# Sheet1.net
KiCad netlist of a schematic drawn in Altium Designer
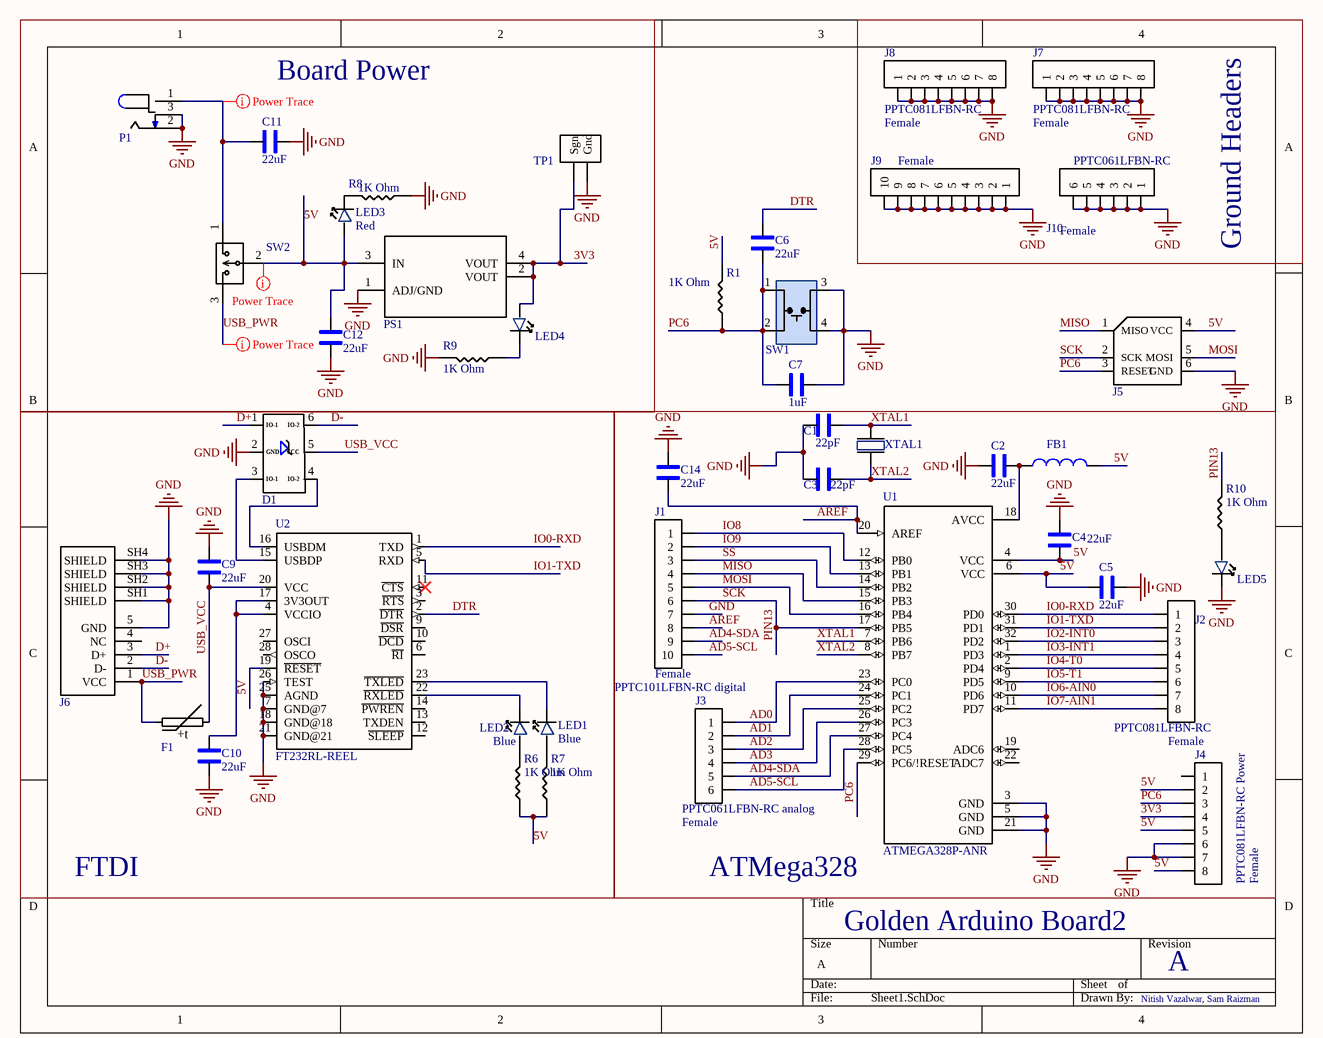
[diagram p0: Sheet1.SchDoc]

(export (version "E")
  (design (tool "Eeschema 10.0.6"))
  (components
    (comp (ref "C1")
      (value "22pF")
      (footprint "0402_Passive")
      (description "MULTILAYER CERAMIC CAPACITORS MLCC - SMD/SMT 22PF 50V 0402 ROHS")
      (fields (field (name "MFR PART #") "0402CG220J500NT") (field (name "LCSC PART#") "C1555"))
      (libsource (lib "ECEN5730Lib_2020_09_AR") (part "C_22pF_0402"))
    )
    (comp (ref "C2")
      (value "22uF")
      (footprint "0603_PASSIVE")
      (description "MULTILAYER CERAMIC CAPACITORS MLCC - SMD/SMT 22UF 6.3V 0603 ROHS")
      (fields (field (name "MFR PART #") "CL10A226MQ8NRNC") (field (name "LCSC PART#") "C59461"))
      (libsource (lib "ECEN5730Lib_2020_09_AR") (part "C_22uF_0603"))
    )
    (comp (ref "C3")
      (value "22pF")
      (footprint "0402_Passive")
      (description "MULTILAYER CERAMIC CAPACITORS MLCC - SMD/SMT 22PF 50V 0402 ROHS")
      (fields (field (name "MFR PART #") "0402CG220J500NT") (field (name "LCSC PART#") "C1555"))
      (libsource (lib "ECEN5730Lib_2020_09_AR") (part "C_22pF_0402"))
    )
    (comp (ref "C4")
      (value "22uF")
      (footprint "0603_PASSIVE")
      (description "MULTILAYER CERAMIC CAPACITORS MLCC - SMD/SMT 22UF 6.3V 0603 ROHS")
      (fields (field (name "MFR PART #") "CL10A226MQ8NRNC") (field (name "LCSC PART#") "C59461"))
      (libsource (lib "ECEN5730Lib_2020_09_AR") (part "C_22uF_0603"))
    )
    (comp (ref "C5")
      (value "22uF")
      (footprint "0603_PASSIVE")
      (description "MULTILAYER CERAMIC CAPACITORS MLCC - SMD/SMT 22UF 6.3V 0603 ROHS")
      (fields (field (name "MFR PART #") "CL10A226MQ8NRNC") (field (name "LCSC PART#") "C59461"))
      (libsource (lib "ECEN5730Lib_2020_09_AR") (part "C_22uF_0603"))
    )
    (comp (ref "C6")
      (value "22uF")
      (footprint "0603_PASSIVE")
      (description "MULTILAYER CERAMIC CAPACITORS MLCC - SMD/SMT 22UF 6.3V 0603 ROHS")
      (fields (field (name "MFR PART #") "CL10A226MQ8NRNC") (field (name "LCSC PART#") "C59461"))
      (libsource (lib "ECEN5730Lib_2020_09_AR") (part "C_22uF_0603"))
    )
    (comp (ref "C7")
      (value "1uF")
      (footprint "0402_Passive")
      (description "MULTILAYER CERAMIC CAPACITORS MLCC - SMD/SMT 1UF 25V 0402 ROHS")
      (fields (field (name "MFR PART #") "CL05A105KA5NQNC") (field (name "LCSC PART#") "C52923"))
      (libsource (lib "ECEN5730Lib_2020_09_AR") (part "C_1uF_0402"))
    )
    (comp (ref "C9")
      (value "22uF")
      (footprint "0603_PASSIVE")
      (description "MULTILAYER CERAMIC CAPACITORS MLCC - SMD/SMT 22UF 6.3V 0603 ROHS")
      (fields (field (name "MFR PART #") "CL10A226MQ8NRNC") (field (name "LCSC PART#") "C59461"))
      (libsource (lib "ECEN5730Lib_2020_09_AR") (part "C_22uF_0603"))
    )
    (comp (ref "C10")
      (value "22uF")
      (footprint "0603_PASSIVE")
      (description "MULTILAYER CERAMIC CAPACITORS MLCC - SMD/SMT 22UF 6.3V 0603 ROHS")
      (fields (field (name "MFR PART #") "CL10A226MQ8NRNC") (field (name "LCSC PART#") "C59461"))
      (libsource (lib "ECEN5730Lib_2020_09_AR") (part "C_22uF_0603"))
    )
    (comp (ref "C11")
      (value "22uF")
      (footprint "0603_PASSIVE")
      (description "MULTILAYER CERAMIC CAPACITORS MLCC - SMD/SMT 22UF 6.3V 0603 ROHS")
      (fields (field (name "MFR PART #") "CL10A226MQ8NRNC") (field (name "LCSC PART#") "C59461"))
      (libsource (lib "ECEN5730Lib_2020_09_AR") (part "C_22uF_0603"))
    )
    (comp (ref "C12")
      (value "22uF")
      (footprint "0603_PASSIVE")
      (description "MULTILAYER CERAMIC CAPACITORS MLCC - SMD/SMT 22UF 6.3V 0603 ROHS")
      (fields (field (name "MFR PART #") "CL10A226MQ8NRNC") (field (name "LCSC PART#") "C59461"))
      (libsource (lib "ECEN5730Lib_2020_09_AR") (part "C_22uF_0603"))
    )
    (comp (ref "C14")
      (value "22uF")
      (footprint "0603_PASSIVE")
      (description "MULTILAYER CERAMIC CAPACITORS MLCC - SMD/SMT 22UF 6.3V 0603 ROHS")
      (fields (field (name "MFR PART #") "CL10A226MQ8NRNC") (field (name "LCSC PART#") "C59461"))
      (libsource (lib "ECEN5730Lib_2020_09_AR") (part "C_22uF_0603"))
    )
    (comp (ref "D1")
      (value "IP4234CZ6,125")
      (footprint "TVS")
      (description "Clamp Ipp Tvs Diode Surface Mount 6-TSOP")
      (fields (field (name "DIGIKEY PART") "1727-4717-1-ND") (field (name "LCSC PART#") "C455086"))
      (libsource (lib "ECEN5730Lib_2020_09_AR") (part "D_TVS_Diode"))
    )
    (comp (ref "F1")
      (value "MF-MSMF050-2")
      (footprint "FUSE")
      (description "Polymeric PTC Resettable Fuse 15V 500mA Ih Surface Mount 1812 (4532 Metric), Concave")
      (fields (field (name "DIGIKEY PART") "MF-MSMF050-2CT-ND") (field (name "MFR PART #") "SMD1812P050TF"))
      (libsource (lib "ECEN5730Lib_2020_09_AR") (part "F_Polyswitch_500mA"))
    )
    (comp (ref "FB1")
      (value "FB_300mA_1206")
      (footprint "1206_Passive")
      (description "Ferrite Bead. 2 kOhms @ 30MHz, 500mOhm")
      (fields (field (name "MFR PART #") "NA"))
      (libsource (lib "ECEN5730Lib_2020_09_AR") (part "FB_300mA_1206"))
    )
    (comp (ref "J1")
      (value "PPTC101LFBN-RC digital")
      (footprint "10_PIN_ARDUINO_100MIL")
      (description "10 Position Header Connector 0.100\" (2.54mm) Through Hole Tin")
      (fields (field (name "DIGIKEY PART") "S7008-ND") (field (name "ALTIUM_VALUE") "Female"))
      (libsource (lib "ECEN5730Lib_2020_09_AR") (part "JF_10_PIN_FEMALE_ARDUINO"))
    )
    (comp (ref "J2")
      (value "PPTC081LFBN-RC")
      (footprint "8_PIN_ARDUINO_100MIL")
      (description "8 Position Header Connector 0.100\" (2.54mm) Through Hole Tin")
      (fields (field (name "DIGIKEY PART") "S7006-ND") (field (name "ALTIUM_VALUE") "Female"))
      (libsource (lib "") (part "JF_8_PIN_FEMALE_ARDUINO_1"))
    )
    (comp (ref "J3")
      (value "PPTC061LFBN-RC analog")
      (footprint "6_PIN_ARDUINO_100mil")
      (description "6 Position Header Connector 0.100\" (2.54mm) Through Hole Tin")
      (fields (field (name "DIGIKEY PART") "S7004-ND") (field (name "ALTIUM_VALUE") "Female"))
      (libsource (lib "") (part "JF_6_PIN_FEMALE_ARDUINO_1"))
    )
    (comp (ref "J4")
      (value "PPTC081LFBN-RC Power")
      (footprint "8_PIN_ARDUINO_100MIL")
      (description "8 Position Header Connector 0.100\" (2.54mm) Through Hole Tin")
      (fields (field (name "DIGIKEY PART") "S7006-ND") (field (name "ALTIUM_VALUE") "Female"))
      (libsource (lib "") (part "JF_8_PIN_FEMALE_ARDUINO_1"))
    )
    (comp (ref "J5")
      (value "NRPN032PAEN-RC")
      (footprint "ICSP")
      (description "Connector Header Through Hole 6 position 0.079\" (2.00mm)")
      (fields (field (name "DIGIKEY PART") "S5801-03-ND"))
      (libsource (lib "ECEN5730Lib_2020_09_AR") (part "J_ICSP"))
    )
    (comp (ref "J6")
      (value "XM7D-0512")
      (footprint "USB_2")
      (description "USB - mini B USB 2.0 Receptacle Connector 5 Position Through Hole, Right Angle")
      (fields (field (name "DIGIKEY PART") "OR1205-ND"))
      (libsource (lib "ECEN5730Lib_2020_09_AR") (part "J_USB_2_B_Mini"))
    )
    (comp (ref "J7")
      (value "PPTC081LFBN-RC")
      (footprint "8_PIN_ARDUINO_100MIL")
      (description "8 Position Header Connector 0.100\" (2.54mm) Through Hole Tin")
      (fields (field (name "DIGIKEY PART") "S7006-ND") (field (name "ALTIUM_VALUE") "Female"))
      (libsource (lib "ECEN5730Lib_2020_09_AR") (part "JF_8_PIN_FEMALE_ARDUINO"))
    )
    (comp (ref "J8")
      (value "PPTC081LFBN-RC")
      (footprint "8_PIN_ARDUINO_100MIL")
      (description "8 Position Header Connector 0.100\" (2.54mm) Through Hole Tin")
      (fields (field (name "DIGIKEY PART") "S7006-ND") (field (name "ALTIUM_VALUE") "Female"))
      (libsource (lib "ECEN5730Lib_2020_09_AR") (part "JF_8_PIN_FEMALE_ARDUINO"))
    )
    (comp (ref "J9")
      (value "Female")
      (footprint "10_PIN_ARDUINO_100MIL")
      (description "10 Position Header Connector 0.100\" (2.54mm) Through Hole Tin")
      (fields (field (name "DIGIKEY PART") "S7008-ND") (field (name "Comment") "PPTC101LFBN-RC"))
      (libsource (lib "") (part "JF_10_PIN_FEMALE_ARDUINO_1"))
    )
    (comp (ref "J10")
      (value "PPTC061LFBN-RC")
      (footprint "6_PIN_ARDUINO_100mil")
      (description "6 Position Header Connector 0.100\" (2.54mm) Through Hole Tin")
      (fields (field (name "DIGIKEY PART") "S7004-ND") (field (name "ALTIUM_VALUE") "Female"))
      (libsource (lib "ECEN5730Lib_2020_09_AR") (part "JF_6_PIN_FEMALE_ARDUINO"))
    )
    (comp (ref "LED1")
      (value "Blue")
      (footprint "LED")
      (description "Blue LED Indicator")
      (fields (field (name "Comment") "LTST-C150CKT"))
      (libsource (lib "ECEN5730Lib_2020_09_AR") (part "LED_BLUE_1206"))
    )
    (comp (ref "LED2")
      (value "Blue")
      (footprint "LED")
      (description "Blue LED Indicator")
      (fields (field (name "Comment") "LTST-C150CKT"))
      (libsource (lib "ECEN5730Lib_2020_09_AR") (part "LED_BLUE_1206"))
    )
    (comp (ref "LED3")
      (value "Red")
      (footprint "LED")
      (description "Red 638nm LED Indication - Discrete 1.8V 1206 (3216 Metric)")
      (fields (field (name "DIGIKEY PART") "160-1167-1-ND") (field (name "Comment") "LTST-C150CKT"))
      (libsource (lib "ECEN5730Lib_2020_09_AR") (part "LED_RED_1206"))
    )
    (comp (ref "LED4")
      (value "LTST-C150CKT")
      (footprint "LED")
      (description "Green LED Indicator")
      (libsource (lib "ECEN5730Lib_2020_09_AR") (part "LED_GREEN_1206"))
    )
    (comp (ref "LED5")
      (value "LTST-C150CKT")
      (footprint "LED")
      (description "Green LED Indicator")
      (libsource (lib "ECEN5730Lib_2020_09_AR") (part "LED_GREEN_1206"))
    )
    (comp (ref "P1")
      (value "Power Jack")
      (footprint "Power_Jack")
      (description "Power Barrel Connector Jack 2.10mm ID (0.083\"), 5.50mm OD (0.217\") Through Hole, Right Angle")
      (fields (field (name "DIGIKEY PART") "CP-102A-ND"))
      (libsource (lib "ECEN5730Lib_2020_09_AR") (part "P_Power Jack"))
    )
    (comp (ref "PS1")
      (value "AZ1117CH-3.3TRG1")
      (footprint "LDO")
      (description "Linear Voltage Regulator IC Positive Fixed 1 Output 1A SOT-223")
      (fields
        (field (name "DIGIKEY PART") "AZ1117CH-3.3TRG1DICT-ND")
        (field (name "MFR PART #") "AZ1117CH2-3.3TRG1")
      )
      (libsource (lib "ECEN5730Lib_2020_09_AR") (part "PS_LDO_3v3"))
    )
    (comp (ref "R1")
      (value "1K Ohm")
      (footprint "0402_Passive")
      (description "1 kOhms chip resistor SURFACE MOUNT 1KOHMS ±1% 1/16W 0402 ROHS")
      (fields (field (name "MFR PART #") "0402WGF1001TCE") (field (name "LCSC PART#") "C11702"))
      (libsource (lib "ECEN5730Lib_2020_09_AR") (part "R_1K_0402"))
    )
    (comp (ref "R6")
      (value "1K Ohm")
      (footprint "0402_Passive")
      (description "1 kOhms chip resistor SURFACE MOUNT 1KOHMS ±1% 1/16W 0402 ROHS")
      (fields (field (name "MFR PART #") "0402WGF1001TCE") (field (name "LCSC PART#") "C11702"))
      (libsource (lib "ECEN5730Lib_2020_09_AR") (part "R_1K_0402"))
    )
    (comp (ref "R7")
      (value "1K Ohm")
      (footprint "0402_Passive")
      (description "1 kOhms chip resistor SURFACE MOUNT 1KOHMS ±1% 1/16W 0402 ROHS")
      (fields (field (name "MFR PART #") "0402WGF1001TCE") (field (name "LCSC PART#") "C11702"))
      (libsource (lib "ECEN5730Lib_2020_09_AR") (part "R_1K_0402"))
    )
    (comp (ref "R8")
      (value "1K Ohm")
      (footprint "0402_Passive")
      (description "1 kOhms chip resistor SURFACE MOUNT 1KOHMS ±1% 1/16W 0402 ROHS")
      (fields (field (name "MFR PART #") "0402WGF1001TCE") (field (name "LCSC PART#") "C11702"))
      (libsource (lib "ECEN5730Lib_2020_09_AR") (part "R_1K_0402"))
    )
    (comp (ref "R9")
      (value "1K Ohm")
      (footprint "0402_Passive")
      (description "1 kOhms chip resistor SURFACE MOUNT 1KOHMS ±1% 1/16W 0402 ROHS")
      (fields (field (name "MFR PART #") "0402WGF1001TCE") (field (name "LCSC PART#") "C11702"))
      (libsource (lib "ECEN5730Lib_2020_09_AR") (part "R_1K_0402"))
    )
    (comp (ref "R10")
      (value "1K Ohm")
      (footprint "0402_Passive")
      (description "1 kOhms chip resistor SURFACE MOUNT 1KOHMS ±1% 1/16W 0402 ROHS")
      (fields (field (name "MFR PART #") "0402WGF1001TCE") (field (name "LCSC PART#") "C11702"))
      (libsource (lib "ECEN5730Lib_2020_09_AR") (part "R_1K_0402"))
    )
    (comp (ref "SW1")
      (value "TL3305AF160QG")
      (footprint "Switch_JLC")
      (description "Tactile Switch SPST-NO Top Actuated Surface Mount")
      (fields (field (name "DIGIKEY PART") "EG5350CT-ND") (field (name "MFR PART #") "UK-B0228-G5-160-JZ"))
      (libsource (lib "ECEN5730Lib_2020_09_AR") (part "SW_Push_Button_JLC"))
    )
    (comp (ref "SW2")
      (value "PREC003SAAN-RC")
      (footprint "3_PIN_100mil")
      (description "Connector Header Through Hole 3 position 0.100\" (2.54mm)")
      (fields (field (name "DIGIKEY PART") "S1012EC-03-ND"))
      (libsource (lib "ECEN5730Lib_2020_09_AR") (part "SW_3Pin_100mil_Switch"))
    )
    (comp (ref "TP1")
      (value "10x Probe TP")
      (footprint "TP10x_Probe")
      (description "Test Point 300 mil centers")
      (libsource (lib "ECEN5730Lib_2020_09_AR") (part "TP_10x_Probe"))
    )
    (comp (ref "U1")
      (value "ATMEGA328P-ANR")
      (footprint "ATMega328P")
      (description "AVR AVR® ATmega Microcontroller IC 8-Bit 20MHz 32KB (16K x 16) FLASH 32-TQFP (7x7)")
      (fields (field (name "MFR PART #") "ATMEGA328P-AU") (field (name "LCSC PART#") "C14877"))
      (libsource (lib "ECEN5730Lib_2020_09_AR") (part "U_ATMega328P"))
    )
    (comp (ref "U2")
      (value "FT232RL-REEL")
      (footprint "FTDI")
      (description "USB Bridge, USB to UART USB 2.0 UART Interface 28-SSOP")
      (fields (field (name "DIGIKEY PART") "768-1007-1-ND") (field (name "LCSC PART#") "C8690"))
      (libsource (lib "ECEN5730Lib_2020_09_AR") (part "U_FTDI232"))
    )
    (comp (ref "XTAL1")
      (value "ABLS-16.000MHZ-B4-T")
      (footprint "Crystal")
      (description "16MHz ±30ppm Crystal 18pF 40 Ohms HC-49/US. Use for ECEN 4/5730 Arduino")
      (fields (field (name "DIGIKEY PART") "535-10226-1-ND"))
      (libsource (lib "ECEN5730Lib_2020_09_AR") (part "XTAL_16MHz"))
    )
  )
  (nets
    (net (code "1") (name "/3V3") (class "Default")
      (node (ref "J4") (pin "4") (pinfunction "4_4") (pintype "passive"))
      (node (ref "LED4") (pin "2") (pinfunction "2_2") (pintype "passive"))
      (node (ref "PS1") (pin "2") (pinfunction "VOUT_2") (pintype "power_in"))
      (node (ref "PS1") (pin "4") (pinfunction "VOUT_4") (pintype "power_in"))
      (node (ref "TP1") (pin "1") (pinfunction "Sgn_1") (pintype "passive"))
    )
    (net (code "2") (name "/5V") (class "Default")
      (node (ref "C12") (pin "2") (pinfunction "2_2") (pintype "passive"))
      (node (ref "C4") (pin "1") (pinfunction "1_1") (pintype "passive"))
      (node (ref "C5") (pin "2") (pinfunction "2_2") (pintype "passive"))
      (node (ref "FB1") (pin "2") (pinfunction "2_2") (pintype "passive"))
      (node (ref "J4") (pin "2") (pinfunction "2_2") (pintype "passive"))
      (node (ref "J4") (pin "5") (pinfunction "5_5") (pintype "passive"))
      (node (ref "J4") (pin "8") (pinfunction "8_8") (pintype "passive"))
      (node (ref "J5") (pin "4") (pinfunction "VCC_4") (pintype "passive"))
      (node (ref "LED3") (pin "2") (pinfunction "2_2") (pintype "passive"))
      (node (ref "PS1") (pin "3") (pinfunction "IN_3") (pintype "power_in"))
      (node (ref "R1") (pin "2") (pinfunction "2_2") (pintype "passive"))
      (node (ref "R6") (pin "1") (pinfunction "1_1") (pintype "passive"))
      (node (ref "R7") (pin "1") (pinfunction "1_1") (pintype "passive"))
      (node (ref "SW2") (pin "2") (pinfunction "2_2") (pintype "passive"))
      (node (ref "U1") (pin "4") (pinfunction "VCC_4") (pintype "power_in"))
      (node (ref "U1") (pin "6") (pinfunction "VCC_6") (pintype "power_in"))
      (node (ref "U2") (pin "19") (pinfunction "~{RESET}_19") (pintype "passive"))
    )
    (net (code "3") (name "/AD0") (class "Default")
      (node (ref "J3") (pin "1") (pinfunction "1_1") (pintype "passive"))
      (node (ref "U1") (pin "23") (pinfunction "PC0_23") (pintype "bidirectional"))
    )
    (net (code "4") (name "/AD1") (class "Default")
      (node (ref "J3") (pin "2") (pinfunction "2_2") (pintype "passive"))
      (node (ref "U1") (pin "24") (pinfunction "PC1_24") (pintype "bidirectional"))
    )
    (net (code "5") (name "/AD2") (class "Default")
      (node (ref "J3") (pin "3") (pinfunction "3_3") (pintype "passive"))
      (node (ref "U1") (pin "25") (pinfunction "PC2_25") (pintype "bidirectional"))
    )
    (net (code "6") (name "/AD3") (class "Default")
      (node (ref "J3") (pin "4") (pinfunction "4_4") (pintype "passive"))
      (node (ref "U1") (pin "26") (pinfunction "PC3_26") (pintype "bidirectional"))
    )
    (net (code "7") (name "/AD4-SDA") (class "Default")
      (node (ref "J1") (pin "9") (pinfunction "9_9") (pintype "passive"))
      (node (ref "J3") (pin "5") (pinfunction "5_5") (pintype "passive"))
      (node (ref "U1") (pin "27") (pinfunction "PC4_27") (pintype "bidirectional"))
    )
    (net (code "8") (name "/AD5-SCL") (class "Default")
      (node (ref "J1") (pin "10") (pinfunction "10_10") (pintype "passive"))
      (node (ref "J3") (pin "6") (pinfunction "6_6") (pintype "passive"))
      (node (ref "U1") (pin "28") (pinfunction "PC5_28") (pintype "bidirectional"))
    )
    (net (code "9") (name "/AREF") (class "Default")
      (node (ref "C14") (pin "1") (pinfunction "1_1") (pintype "passive"))
      (node (ref "J1") (pin "8") (pinfunction "8_8") (pintype "passive"))
      (node (ref "U1") (pin "20") (pinfunction "AREF_20") (pintype "input"))
    )
    (net (code "10") (name "/D+") (class "Default")
      (node (ref "D1") (pin "1") (pinfunction "IO-1_1") (pintype "passive"))
      (node (ref "J6") (pin "3") (pinfunction "D+_3") (pintype "passive"))
    )
    (net (code "11") (name "/D-") (class "Default")
      (node (ref "D1") (pin "6") (pinfunction "IO-2_6") (pintype "passive"))
      (node (ref "J6") (pin "2") (pinfunction "D-_2") (pintype "passive"))
    )
    (net (code "12") (name "/DTR") (class "Default")
      (node (ref "C6") (pin "2") (pinfunction "2_2") (pintype "passive"))
      (node (ref "U2") (pin "2") (pinfunction "~{DTR}_2") (pintype "output"))
    )
    (net (code "13") (name "/IO0-RXD") (class "Default")
      (node (ref "J2") (pin "1") (pinfunction "1_1") (pintype "passive"))
      (node (ref "U1") (pin "30") (pinfunction "PD0_30") (pintype "bidirectional"))
      (node (ref "U2") (pin "1") (pinfunction "TXD_1") (pintype "output"))
    )
    (net (code "14") (name "/IO1-TXD") (class "Default")
      (node (ref "J2") (pin "2") (pinfunction "2_2") (pintype "passive"))
      (node (ref "U1") (pin "31") (pinfunction "PD1_31") (pintype "bidirectional"))
      (node (ref "U2") (pin "5") (pinfunction "RXD_5") (pintype "input"))
    )
    (net (code "15") (name "/IO2-INT0") (class "Default")
      (node (ref "J2") (pin "3") (pinfunction "3_3") (pintype "passive"))
      (node (ref "U1") (pin "32") (pinfunction "PD2_32") (pintype "bidirectional"))
    )
    (net (code "16") (name "/IO3-INT1") (class "Default")
      (node (ref "J2") (pin "4") (pinfunction "4_4") (pintype "passive"))
      (node (ref "U1") (pin "1") (pinfunction "PD3_1") (pintype "bidirectional"))
    )
    (net (code "17") (name "/IO4-T0") (class "Default")
      (node (ref "J2") (pin "5") (pinfunction "5_5") (pintype "passive"))
      (node (ref "U1") (pin "2") (pinfunction "PD4_2") (pintype "bidirectional"))
    )
    (net (code "18") (name "/IO5-T1") (class "Default")
      (node (ref "J2") (pin "6") (pinfunction "6_6") (pintype "passive"))
      (node (ref "U1") (pin "9") (pinfunction "PD5_9") (pintype "bidirectional"))
    )
    (net (code "19") (name "/IO6-AIN0") (class "Default")
      (node (ref "J2") (pin "7") (pinfunction "7_7") (pintype "passive"))
      (node (ref "U1") (pin "10") (pinfunction "PD6_10") (pintype "bidirectional"))
    )
    (net (code "20") (name "/IO7-AIN1") (class "Default")
      (node (ref "J2") (pin "8") (pinfunction "8_8") (pintype "passive"))
      (node (ref "U1") (pin "11") (pinfunction "PD7_11") (pintype "bidirectional"))
    )
    (net (code "21") (name "/IO8") (class "Default")
      (node (ref "J1") (pin "1") (pinfunction "1_1") (pintype "passive"))
      (node (ref "U1") (pin "12") (pinfunction "PB0_12") (pintype "bidirectional"))
    )
    (net (code "22") (name "/IO9") (class "Default")
      (node (ref "J1") (pin "2") (pinfunction "2_2") (pintype "passive"))
      (node (ref "U1") (pin "13") (pinfunction "PB1_13") (pintype "bidirectional"))
    )
    (net (code "23") (name "/MISO") (class "Default")
      (node (ref "J1") (pin "4") (pinfunction "4_4") (pintype "passive"))
      (node (ref "J5") (pin "1") (pinfunction "MISO_1") (pintype "passive"))
      (node (ref "U1") (pin "15") (pinfunction "PB3_15") (pintype "bidirectional"))
    )
    (net (code "24") (name "/MOSI") (class "Default")
      (node (ref "J1") (pin "5") (pinfunction "5_5") (pintype "passive"))
      (node (ref "J5") (pin "5") (pinfunction "MOSI_5") (pintype "passive"))
      (node (ref "U1") (pin "16") (pinfunction "PB4_16") (pintype "bidirectional"))
    )
    (net (code "25") (name "/PC6") (class "Default")
      (node (ref "C6") (pin "1") (pinfunction "1_1") (pintype "passive"))
      (node (ref "C7") (pin "1") (pinfunction "1_1") (pintype "passive"))
      (node (ref "J4") (pin "3") (pinfunction "3_3") (pintype "passive"))
      (node (ref "J5") (pin "3") (pinfunction "RESET_3") (pintype "passive"))
      (node (ref "R1") (pin "1") (pinfunction "1_1") (pintype "passive"))
      (node (ref "SW1") (pin "1") (pinfunction "1_1") (pintype "passive"))
      (node (ref "SW1") (pin "2") (pinfunction "2_2") (pintype "passive"))
      (node (ref "U1") (pin "29") (pinfunction "PC6/!RESET_29") (pintype "bidirectional"))
    )
    (net (code "26") (name "/PIN13") (class "Default")
      (node (ref "J1") (pin "6") (pinfunction "6_6") (pintype "passive"))
      (node (ref "J5") (pin "2") (pinfunction "SCK_2") (pintype "passive"))
      (node (ref "R10") (pin "2") (pinfunction "2_2") (pintype "passive"))
      (node (ref "U1") (pin "17") (pinfunction "PB5_17") (pintype "bidirectional"))
    )
    (net (code "27") (name "/SS") (class "Default")
      (node (ref "J1") (pin "3") (pinfunction "3_3") (pintype "passive"))
      (node (ref "U1") (pin "14") (pinfunction "PB2_14") (pintype "bidirectional"))
    )
    (net (code "28") (name "/USB_PWR") (class "Default")
      (node (ref "F1") (pin "1") (pinfunction "1_1") (pintype "passive"))
      (node (ref "J6") (pin "1") (pinfunction "VCC_1") (pintype "passive"))
      (node (ref "SW2") (pin "3") (pinfunction "3_3") (pintype "passive"))
    )
    (net (code "29") (name "/USB_VCC") (class "Default")
      (node (ref "C9") (pin "1") (pinfunction "1_1") (pintype "passive"))
      (node (ref "D1") (pin "5") (pinfunction "VCC_5") (pintype "passive"))
      (node (ref "F1") (pin "2") (pinfunction "2_2") (pintype "passive"))
      (node (ref "U2") (pin "20") (pinfunction "VCC_20") (pintype "power_in"))
    )
    (net (code "30") (name "/XTAL1") (class "Default")
      (node (ref "C1") (pin "2") (pinfunction "2_2") (pintype "passive"))
      (node (ref "U1") (pin "7") (pinfunction "PB6_7") (pintype "bidirectional"))
      (node (ref "XTAL1") (pin "2") (pinfunction "2_2") (pintype "passive"))
    )
    (net (code "31") (name "/XTAL2") (class "Default")
      (node (ref "C3") (pin "2") (pinfunction "2_2") (pintype "passive"))
      (node (ref "U1") (pin "8") (pinfunction "PB7_8") (pintype "bidirectional"))
      (node (ref "XTAL1") (pin "1") (pinfunction "1_1") (pintype "passive"))
    )
    (net (code "32") (name "GND") (class "Default")
      (node (ref "C1") (pin "1") (pinfunction "1_1") (pintype "passive"))
      (node (ref "C10") (pin "1") (pinfunction "1_1") (pintype "passive"))
      (node (ref "C11") (pin "2") (pinfunction "2_2") (pintype "passive"))
      (node (ref "C12") (pin "1") (pinfunction "1_1") (pintype "passive"))
      (node (ref "C14") (pin "2") (pinfunction "2_2") (pintype "passive"))
      (node (ref "C2") (pin "1") (pinfunction "1_1") (pintype "passive"))
      (node (ref "C3") (pin "1") (pinfunction "1_1") (pintype "passive"))
      (node (ref "C4") (pin "2") (pinfunction "2_2") (pintype "passive"))
      (node (ref "C5") (pin "1") (pinfunction "1_1") (pintype "passive"))
      (node (ref "C7") (pin "2") (pinfunction "2_2") (pintype "passive"))
      (node (ref "C9") (pin "2") (pinfunction "2_2") (pintype "passive"))
      (node (ref "D1") (pin "2") (pinfunction "GND_2") (pintype "passive"))
      (node (ref "J1") (pin "7") (pinfunction "7_7") (pintype "passive"))
      (node (ref "J10") (pin "1") (pinfunction "1_1") (pintype "passive"))
      (node (ref "J10") (pin "2") (pinfunction "2_2") (pintype "passive"))
      (node (ref "J10") (pin "3") (pinfunction "3_3") (pintype "passive"))
      (node (ref "J10") (pin "4") (pinfunction "4_4") (pintype "passive"))
      (node (ref "J10") (pin "5") (pinfunction "5_5") (pintype "passive"))
      (node (ref "J10") (pin "6") (pinfunction "6_6") (pintype "passive"))
      (node (ref "J4") (pin "6") (pinfunction "6_6") (pintype "passive"))
      (node (ref "J4") (pin "7") (pinfunction "7_7") (pintype "passive"))
      (node (ref "J5") (pin "6") (pinfunction "GND_6") (pintype "passive"))
      (node (ref "J6") (pin "5") (pinfunction "GND_5") (pintype "passive"))
      (node (ref "J6") (pin "SH1") (pinfunction "SHIELD_SH1") (pintype "passive"))
      (node (ref "J6") (pin "SH2") (pinfunction "SHIELD_SH2") (pintype "passive"))
      (node (ref "J6") (pin "SH3") (pinfunction "SHIELD_SH3") (pintype "passive"))
      (node (ref "J6") (pin "SH4") (pinfunction "SHIELD_SH4") (pintype "passive"))
      (node (ref "J7") (pin "1") (pinfunction "1_1") (pintype "passive"))
      (node (ref "J7") (pin "2") (pinfunction "2_2") (pintype "passive"))
      (node (ref "J7") (pin "3") (pinfunction "3_3") (pintype "passive"))
      (node (ref "J7") (pin "4") (pinfunction "4_4") (pintype "passive"))
      (node (ref "J7") (pin "5") (pinfunction "5_5") (pintype "passive"))
      (node (ref "J7") (pin "6") (pinfunction "6_6") (pintype "passive"))
      (node (ref "J7") (pin "7") (pinfunction "7_7") (pintype "passive"))
      (node (ref "J7") (pin "8") (pinfunction "8_8") (pintype "passive"))
      (node (ref "J8") (pin "1") (pinfunction "1_1") (pintype "passive"))
      (node (ref "J8") (pin "2") (pinfunction "2_2") (pintype "passive"))
      (node (ref "J8") (pin "3") (pinfunction "3_3") (pintype "passive"))
      (node (ref "J8") (pin "4") (pinfunction "4_4") (pintype "passive"))
      (node (ref "J8") (pin "5") (pinfunction "5_5") (pintype "passive"))
      (node (ref "J8") (pin "6") (pinfunction "6_6") (pintype "passive"))
      (node (ref "J8") (pin "7") (pinfunction "7_7") (pintype "passive"))
      (node (ref "J8") (pin "8") (pinfunction "8_8") (pintype "passive"))
      (node (ref "J9") (pin "1") (pinfunction "1_1") (pintype "passive"))
      (node (ref "J9") (pin "10") (pinfunction "10_10") (pintype "passive"))
      (node (ref "J9") (pin "2") (pinfunction "2_2") (pintype "passive"))
      (node (ref "J9") (pin "3") (pinfunction "3_3") (pintype "passive"))
      (node (ref "J9") (pin "4") (pinfunction "4_4") (pintype "passive"))
      (node (ref "J9") (pin "5") (pinfunction "5_5") (pintype "passive"))
      (node (ref "J9") (pin "6") (pinfunction "6_6") (pintype "passive"))
      (node (ref "J9") (pin "7") (pinfunction "7_7") (pintype "passive"))
      (node (ref "J9") (pin "8") (pinfunction "8_8") (pintype "passive"))
      (node (ref "J9") (pin "9") (pinfunction "9_9") (pintype "passive"))
      (node (ref "LED5") (pin "1") (pinfunction "1_1") (pintype "passive"))
      (node (ref "P1") (pin "2") (pinfunction "2_2") (pintype "power_in"))
      (node (ref "P1") (pin "3") (pinfunction "3_3") (pintype "power_in"))
      (node (ref "PS1") (pin "1") (pinfunction "ADJ/GND_1") (pintype "passive"))
      (node (ref "R8") (pin "1") (pinfunction "1_1") (pintype "passive"))
      (node (ref "R9") (pin "2") (pinfunction "2_2") (pintype "passive"))
      (node (ref "SW1") (pin "3") (pinfunction "3_3") (pintype "passive"))
      (node (ref "SW1") (pin "4") (pinfunction "4_4") (pintype "passive"))
      (node (ref "TP1") (pin "2") (pinfunction "Gnd_2") (pintype "passive"))
      (node (ref "U1") (pin "21") (pinfunction "GND_21") (pintype "power_in"))
      (node (ref "U1") (pin "3") (pinfunction "GND_3") (pintype "power_in"))
      (node (ref "U1") (pin "5") (pinfunction "GND_5") (pintype "power_in"))
      (node (ref "U2") (pin "18") (pinfunction "GND@18_18") (pintype "power_in"))
      (node (ref "U2") (pin "21") (pinfunction "GND@21_21") (pintype "power_in"))
      (node (ref "U2") (pin "25") (pinfunction "AGND_25") (pintype "power_in"))
      (node (ref "U2") (pin "26") (pinfunction "TEST_26") (pintype "input"))
      (node (ref "U2") (pin "7") (pinfunction "GND@7_7") (pintype "power_in"))
    )
    (net (code "33") (name "Net-(C11-Pad1)") (class "Default")
      (node (ref "C11") (pin "1") (pinfunction "1_1") (pintype "passive"))
      (node (ref "P1") (pin "1") (pinfunction "1_1") (pintype "power_in"))
      (node (ref "SW2") (pin "1") (pinfunction "1_1") (pintype "passive"))
    )
    (net (code "34") (name "Net-(LED1-Pad2)") (class "Default")
      (node (ref "LED1") (pin "2") (pinfunction "2_2") (pintype "passive"))
      (node (ref "R7") (pin "2") (pinfunction "2_2") (pintype "passive"))
    )
    (net (code "35") (name "Net-(LED2-Pad2)") (class "Default")
      (node (ref "LED2") (pin "2") (pinfunction "2_2") (pintype "passive"))
      (node (ref "R6") (pin "2") (pinfunction "2_2") (pintype "passive"))
    )
    (net (code "36") (name "Net-(LED3-Pad1)") (class "Default")
      (node (ref "LED3") (pin "1") (pinfunction "1_1") (pintype "passive"))
      (node (ref "R8") (pin "2") (pinfunction "2_2") (pintype "passive"))
    )
    (net (code "37") (name "Net-(LED4-Pad1)") (class "Default")
      (node (ref "LED4") (pin "1") (pinfunction "1_1") (pintype "passive"))
      (node (ref "R9") (pin "1") (pinfunction "1_1") (pintype "passive"))
    )
    (net (code "38") (name "Net-(LED5-Pad2)") (class "Default")
      (node (ref "LED5") (pin "2") (pinfunction "2_2") (pintype "passive"))
      (node (ref "R10") (pin "1") (pinfunction "1_1") (pintype "passive"))
    )
    (net (code "39") (name "Net-(U1-AVCC)") (class "Default")
      (node (ref "C2") (pin "2") (pinfunction "2_2") (pintype "passive"))
      (node (ref "FB1") (pin "1") (pinfunction "1_1") (pintype "passive"))
      (node (ref "U1") (pin "18") (pinfunction "AVCC_18") (pintype "power_in"))
    )
    (net (code "40") (name "Net-(U2-3V3OUT)") (class "Default")
      (node (ref "C10") (pin "2") (pinfunction "2_2") (pintype "passive"))
      (node (ref "U2") (pin "17") (pinfunction "3V3OUT_17") (pintype "passive"))
      (node (ref "U2") (pin "4") (pinfunction "VCCIO_4") (pintype "power_in"))
    )
    (net (code "41") (name "Net-(U2-USBDM)") (class "Default")
      (node (ref "D1") (pin "4") (pinfunction "IO-2_4") (pintype "passive"))
      (node (ref "U2") (pin "16") (pinfunction "USBDM_16") (pintype "bidirectional"))
    )
    (net (code "42") (name "Net-(U2-USBDP)") (class "Default")
      (node (ref "D1") (pin "3") (pinfunction "IO-1_3") (pintype "passive"))
      (node (ref "U2") (pin "15") (pinfunction "USBDP_15") (pintype "bidirectional"))
    )
    (net (code "43") (name "Net-(U2-~{RXLED})") (class "Default")
      (node (ref "LED2") (pin "1") (pinfunction "1_1") (pintype "passive"))
      (node (ref "U2") (pin "22") (pinfunction "~{RXLED}_22") (pintype "passive"))
    )
    (net (code "44") (name "Net-(U2-~{TXLED})") (class "Default")
      (node (ref "LED1") (pin "1") (pinfunction "1_1") (pintype "passive"))
      (node (ref "U2") (pin "23") (pinfunction "~{TXLED}_23") (pintype "passive"))
    )
    (net (code "45") (name "unconnected-(J4-Pad1)") (class "Default")
      (node (ref "J4") (pin "1") (pinfunction "1_1") (pintype "passive"))
    )
    (net (code "46") (name "unconnected-(J6-NC-Pad4)") (class "Default")
      (node (ref "J6") (pin "4") (pinfunction "NC_4") (pintype "passive"))
    )
    (net (code "47") (name "unconnected-(U1-ADC6-Pad19)") (class "Default")
      (node (ref "U1") (pin "19") (pinfunction "ADC6_19") (pintype "bidirectional"))
    )
    (net (code "48") (name "unconnected-(U1-ADC7-Pad22)") (class "Default")
      (node (ref "U1") (pin "22") (pinfunction "ADC7_22") (pintype "bidirectional"))
    )
    (net (code "49") (name "unconnected-(U2-OSCI-Pad27)") (class "Default")
      (node (ref "U2") (pin "27") (pinfunction "OSCI_27") (pintype "passive"))
    )
    (net (code "50") (name "unconnected-(U2-OSCO-Pad28)") (class "Default")
      (node (ref "U2") (pin "28") (pinfunction "OSCO_28") (pintype "output"))
    )
    (net (code "51") (name "unconnected-(U2-TXDEN-Pad13)") (class "Default")
      (node (ref "U2") (pin "13") (pinfunction "TXDEN_13") (pintype "passive"))
    )
    (net (code "52") (name "unconnected-(U2-~{CTS}-Pad11)") (class "Default")
      (node (ref "U2") (pin "11") (pinfunction "~{CTS}_11") (pintype "input+no_connect"))
    )
    (net (code "53") (name "unconnected-(U2-~{DCD}-Pad10)") (class "Default")
      (node (ref "U2") (pin "10") (pinfunction "~{DCD}_10") (pintype "passive"))
    )
    (net (code "54") (name "unconnected-(U2-~{DSR}-Pad9)") (class "Default")
      (node (ref "U2") (pin "9") (pinfunction "~{DSR}_9") (pintype "passive"))
    )
    (net (code "55") (name "unconnected-(U2-~{PWREN}-Pad14)") (class "Default")
      (node (ref "U2") (pin "14") (pinfunction "~{PWREN}_14") (pintype "passive"))
    )
    (net (code "56") (name "unconnected-(U2-~{RI}-Pad6)") (class "Default")
      (node (ref "U2") (pin "6") (pinfunction "~{RI}_6") (pintype "passive"))
    )
    (net (code "57") (name "unconnected-(U2-~{RTS}-Pad3)") (class "Default")
      (node (ref "U2") (pin "3") (pinfunction "~{RTS}_3") (pintype "output"))
    )
    (net (code "58") (name "unconnected-(U2-~{SLEEP}-Pad12)") (class "Default")
      (node (ref "U2") (pin "12") (pinfunction "~{SLEEP}_12") (pintype "passive"))
    )
  )
)
